# kitchen_timer.net
KiCad netlist of a schematic drawn in EAGLE
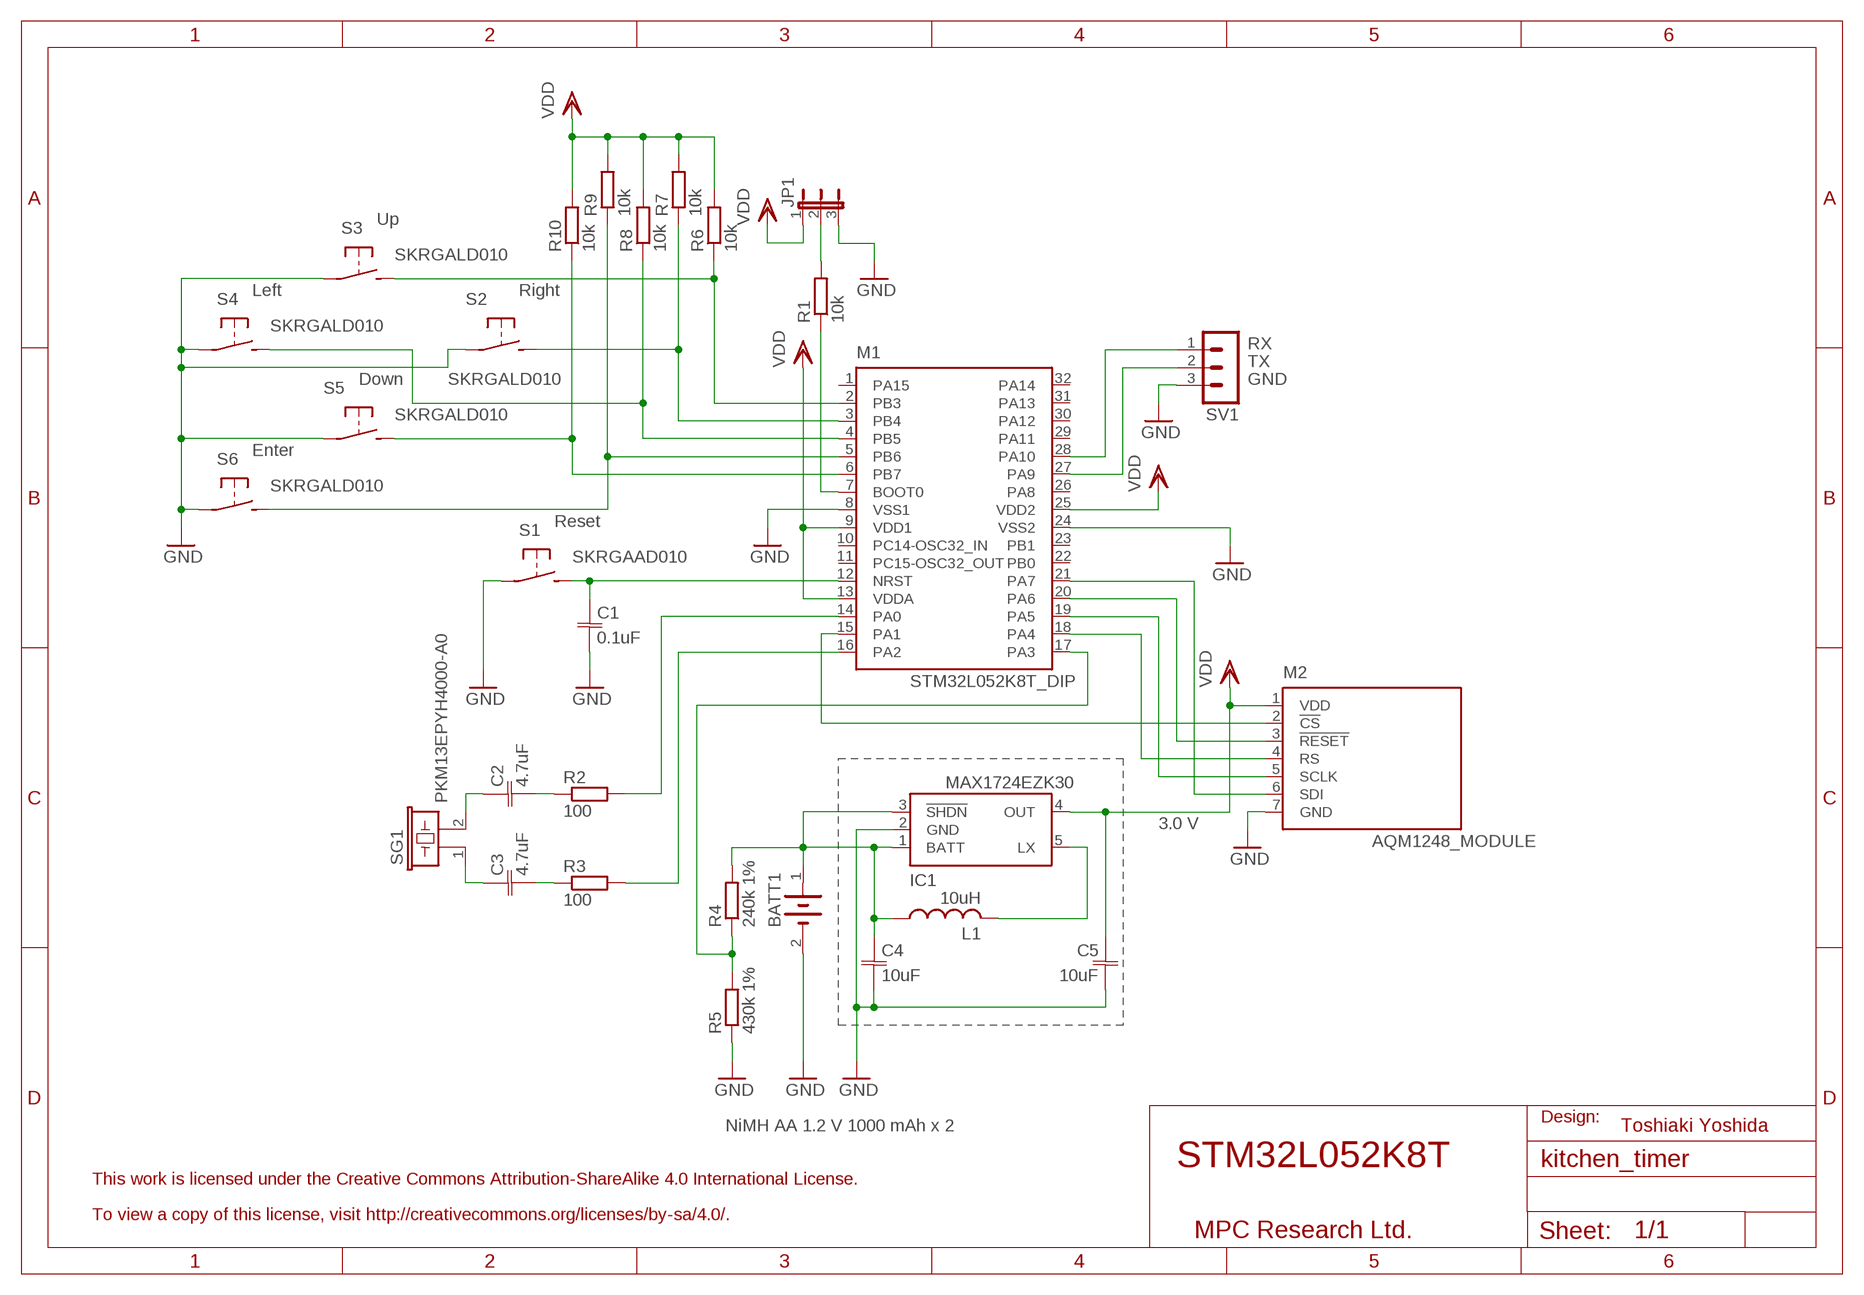
[diagram p0: schematic, sheet 1]

(export (version "E")
  (design (tool "Eeschema 10.0.6"))
  (components
    (comp (ref "BATT1")
      (value "NiMH AA 1.2 V 1000 mAh x 2")
      (footprint "eagle-import:TERMINAL")
      (libsource (lib "eagle-import") (part "BATTERY2"))
    )
    (comp (ref "C1")
      (value "0.1uF")
      (footprint "eagle-import:C050-024X044")
      (libsource (lib "eagle-import") (part "C-JIS050-024X044"))
    )
    (comp (ref "C2")
      (value "4.7uF")
      (footprint "eagle-import:C050-024X044")
      (libsource (lib "eagle-import") (part "C-JIS050-024X044"))
    )
    (comp (ref "C3")
      (value "4.7uF")
      (footprint "eagle-import:C050-024X044")
      (libsource (lib "eagle-import") (part "C-JIS050-024X044"))
    )
    (comp (ref "C4")
      (value "10uF")
      (footprint "eagle-import:C0603")
      (libsource (lib "eagle-import") (part "C-JIS0603"))
    )
    (comp (ref "C5")
      (value "10uF")
      (footprint "eagle-import:C0603")
      (libsource (lib "eagle-import") (part "C-JIS0603"))
    )
    (comp (ref "IC1")
      (value "MAX1724EZK30")
      (footprint "eagle-import:SOT23-5L")
      (libsource (lib "eagle-import") (part "MAX1724EZK30"))
    )
    (comp (ref "JP1")
      (value "JP2E")
      (footprint "eagle-import:JP2")
      (libsource (lib "eagle-import") (part "JP2E"))
    )
    (comp (ref "L1")
      (value "10uH")
      (footprint "eagle-import:L1812")
      (libsource (lib "eagle-import") (part "L-USL1812"))
    )
    (comp (ref "M1")
      (value "STM32L052K8T_DIP")
      (footprint "eagle-import:DIP32")
      (libsource (lib "eagle-import") (part "STM32L052K8T_DIP"))
    )
    (comp (ref "M2")
      (value "AQM1248_MODULE")
      (footprint "eagle-import:AQM1248")
      (libsource (lib "eagle-import") (part "AQM1248_MODULE"))
    )
    (comp (ref "R1")
      (value "10k")
      (footprint "eagle-import:0207_2V")
      (libsource (lib "eagle-import") (part "R-EU_0207/2V"))
    )
    (comp (ref "R2")
      (value "100")
      (footprint "eagle-import:0207_10")
      (libsource (lib "eagle-import") (part "R-EU_0207/10"))
    )
    (comp (ref "R3")
      (value "100")
      (footprint "eagle-import:0207_10")
      (libsource (lib "eagle-import") (part "R-EU_0207/10"))
    )
    (comp (ref "R4")
      (value "240k 1%")
      (footprint "eagle-import:0207_2V")
      (libsource (lib "eagle-import") (part "R-EU_0207/2V"))
    )
    (comp (ref "R5")
      (value "430k 1%")
      (footprint "eagle-import:0207_2V")
      (libsource (lib "eagle-import") (part "R-EU_0207/2V"))
    )
    (comp (ref "R6")
      (value "10k")
      (footprint "eagle-import:0207_7")
      (libsource (lib "eagle-import") (part "resistor_348_R-EU_0207/7"))
    )
    (comp (ref "R7")
      (value "10k")
      (footprint "eagle-import:0207_7")
      (libsource (lib "eagle-import") (part "resistor_348_R-EU_0207/7"))
    )
    (comp (ref "R8")
      (value "10k")
      (footprint "eagle-import:0207_7")
      (libsource (lib "eagle-import") (part "resistor_348_R-EU_0207/7"))
    )
    (comp (ref "R9")
      (value "10k")
      (footprint "eagle-import:0207_7")
      (libsource (lib "eagle-import") (part "resistor_348_R-EU_0207/7"))
    )
    (comp (ref "R10")
      (value "10k")
      (footprint "eagle-import:0207_7")
      (libsource (lib "eagle-import") (part "resistor_348_R-EU_0207/7"))
    )
    (comp (ref "S1")
      (value "SKRGAAD010")
      (footprint "eagle-import:SKRG")
      (libsource (lib "eagle-import") (part "SKRGAAD010"))
    )
    (comp (ref "S2")
      (value "SKRGALD010")
      (footprint "eagle-import:SKRG")
      (libsource (lib "eagle-import") (part "SKRGALD010"))
    )
    (comp (ref "S3")
      (value "SKRGALD010")
      (footprint "eagle-import:SKRG")
      (libsource (lib "eagle-import") (part "SKRGALD010"))
    )
    (comp (ref "S4")
      (value "SKRGALD010")
      (footprint "eagle-import:SKRG")
      (libsource (lib "eagle-import") (part "SKRGALD010"))
    )
    (comp (ref "S5")
      (value "SKRGALD010")
      (footprint "eagle-import:SKRG")
      (libsource (lib "eagle-import") (part "SKRGALD010"))
    )
    (comp (ref "S6")
      (value "SKRGALD010")
      (footprint "eagle-import:SKRG")
      (libsource (lib "eagle-import") (part "SKRGALD010"))
    )
    (comp (ref "SG1")
      (value "PKM13EPYH4000-A0")
      (footprint "eagle-import:EFBAA40D101")
      (libsource (lib "eagle-import") (part "EFB?AA40D101"))
    )
    (comp (ref "SV1")
      (value "MA03-1")
      (footprint "eagle-import:MA03-1")
      (libsource (lib "eagle-import") (part "MA03-1"))
    )
  )
  (nets
    (net (code "1") (name "GND") (class "Default")
      (node (ref "BATT1") (pin "2") (pinfunction "-_2") (pintype "passive"))
      (node (ref "C1") (pin "2") (pinfunction "2_2") (pintype "passive"))
      (node (ref "C4") (pin "2") (pinfunction "2_2") (pintype "passive"))
      (node (ref "C5") (pin "2") (pinfunction "2_2") (pintype "passive"))
      (node (ref "IC1") (pin "2") (pinfunction "GND_2") (pintype "power_in"))
      (node (ref "JP1") (pin "3") (pinfunction "3_3") (pintype "passive"))
      (node (ref "M1") (pin "24") (pinfunction "VSS2_24") (pintype "power_in"))
      (node (ref "M1") (pin "8") (pinfunction "VSS1_8") (pintype "power_in"))
      (node (ref "M2") (pin "7") (pinfunction "GND_7") (pintype "power_in"))
      (node (ref "R5") (pin "1") (pinfunction "1_1") (pintype "passive"))
      (node (ref "S1") (pin "P$1") (pinfunction "1_P$1") (pintype "passive"))
      (node (ref "S2") (pin "P$1") (pinfunction "1_P$1") (pintype "passive"))
      (node (ref "S3") (pin "P$1") (pinfunction "1_P$1") (pintype "passive"))
      (node (ref "S4") (pin "P$1") (pinfunction "1_P$1") (pintype "passive"))
      (node (ref "S5") (pin "P$1") (pinfunction "1_P$1") (pintype "passive"))
      (node (ref "S6") (pin "P$1") (pinfunction "1_P$1") (pintype "passive"))
      (node (ref "SV1") (pin "3") (pinfunction "3_3") (pintype "passive"))
    )
    (net (code "2") (name "Net-(BATT1-+)") (class "Default")
      (node (ref "BATT1") (pin "1") (pinfunction "+_1") (pintype "passive"))
      (node (ref "C4") (pin "1") (pinfunction "1_1") (pintype "passive"))
      (node (ref "IC1") (pin "1") (pinfunction "BATT_1") (pintype "power_in"))
      (node (ref "IC1") (pin "3") (pinfunction "~{SHDN}_3") (pintype "input"))
      (node (ref "L1") (pin "1") (pinfunction "1_1") (pintype "passive"))
      (node (ref "R4") (pin "2") (pinfunction "2_2") (pintype "passive"))
    )
    (net (code "3") (name "Net-(C2-Pad1)") (class "Default")
      (node (ref "C2") (pin "1") (pinfunction "1_1") (pintype "passive"))
      (node (ref "SG1") (pin "2") (pinfunction "2_2") (pintype "passive"))
    )
    (net (code "4") (name "Net-(C2-Pad2)") (class "Default")
      (node (ref "C2") (pin "2") (pinfunction "2_2") (pintype "passive"))
      (node (ref "R2") (pin "1") (pinfunction "1_1") (pintype "passive"))
    )
    (net (code "5") (name "Net-(C3-Pad1)") (class "Default")
      (node (ref "C3") (pin "1") (pinfunction "1_1") (pintype "passive"))
      (node (ref "SG1") (pin "1") (pinfunction "1_1") (pintype "passive"))
    )
    (net (code "6") (name "Net-(C3-Pad2)") (class "Default")
      (node (ref "C3") (pin "2") (pinfunction "2_2") (pintype "passive"))
      (node (ref "R3") (pin "1") (pinfunction "1_1") (pintype "passive"))
    )
    (net (code "7") (name "Net-(IC1-LX)") (class "Default")
      (node (ref "IC1") (pin "5") (pinfunction "LX_5") (pintype "bidirectional"))
      (node (ref "L1") (pin "2") (pinfunction "2_2") (pintype "passive"))
    )
    (net (code "8") (name "Net-(JP1-Pad2)") (class "Default")
      (node (ref "JP1") (pin "2") (pinfunction "2_2") (pintype "passive"))
      (node (ref "R1") (pin "2") (pinfunction "2_2") (pintype "passive"))
    )
    (net (code "9") (name "Net-(M1-BOOT0)") (class "Default")
      (node (ref "M1") (pin "7") (pinfunction "BOOT0_7") (pintype "bidirectional"))
      (node (ref "R1") (pin "1") (pinfunction "1_1") (pintype "passive"))
    )
    (net (code "10") (name "Net-(M1-NRST)") (class "Default")
      (node (ref "C1") (pin "1") (pinfunction "1_1") (pintype "passive"))
      (node (ref "M1") (pin "12") (pinfunction "NRST_12") (pintype "bidirectional"))
      (node (ref "S1") (pin "P$2") (pinfunction "2_P$2") (pintype "passive"))
    )
    (net (code "11") (name "Net-(M1-PA0)") (class "Default")
      (node (ref "M1") (pin "14") (pinfunction "PA0_14") (pintype "bidirectional"))
      (node (ref "R2") (pin "2") (pinfunction "2_2") (pintype "passive"))
    )
    (net (code "12") (name "Net-(M1-PA1)") (class "Default")
      (node (ref "M1") (pin "15") (pinfunction "PA1_15") (pintype "bidirectional"))
      (node (ref "M2") (pin "2") (pinfunction "~{CS}_2") (pintype "input"))
    )
    (net (code "13") (name "Net-(M1-PA2)") (class "Default")
      (node (ref "M1") (pin "16") (pinfunction "PA2_16") (pintype "bidirectional"))
      (node (ref "R3") (pin "2") (pinfunction "2_2") (pintype "passive"))
    )
    (net (code "14") (name "Net-(M1-PA3)") (class "Default")
      (node (ref "M1") (pin "17") (pinfunction "PA3_17") (pintype "bidirectional"))
      (node (ref "R4") (pin "1") (pinfunction "1_1") (pintype "passive"))
      (node (ref "R5") (pin "2") (pinfunction "2_2") (pintype "passive"))
    )
    (net (code "15") (name "Net-(M1-PA4)") (class "Default")
      (node (ref "M1") (pin "18") (pinfunction "PA4_18") (pintype "bidirectional"))
      (node (ref "M2") (pin "4") (pinfunction "RS_4") (pintype "input"))
    )
    (net (code "16") (name "Net-(M1-PA5)") (class "Default")
      (node (ref "M1") (pin "19") (pinfunction "PA5_19") (pintype "bidirectional"))
      (node (ref "M2") (pin "5") (pinfunction "SCLK_5") (pintype "input"))
    )
    (net (code "17") (name "Net-(M1-PA6)") (class "Default")
      (node (ref "M1") (pin "20") (pinfunction "PA6_20") (pintype "bidirectional"))
      (node (ref "M2") (pin "3") (pinfunction "~{RESET}_3") (pintype "input"))
    )
    (net (code "18") (name "Net-(M1-PA7)") (class "Default")
      (node (ref "M1") (pin "21") (pinfunction "PA7_21") (pintype "bidirectional"))
      (node (ref "M2") (pin "6") (pinfunction "SDI_6") (pintype "input"))
    )
    (net (code "19") (name "Net-(M1-PA9)") (class "Default")
      (node (ref "M1") (pin "27") (pinfunction "PA9_27") (pintype "bidirectional"))
      (node (ref "SV1") (pin "2") (pinfunction "2_2") (pintype "passive"))
    )
    (net (code "20") (name "Net-(M1-PA10)") (class "Default")
      (node (ref "M1") (pin "28") (pinfunction "PA10_28") (pintype "bidirectional"))
      (node (ref "SV1") (pin "1") (pinfunction "1_1") (pintype "passive"))
    )
    (net (code "21") (name "Net-(M1-PB3)") (class "Default")
      (node (ref "M1") (pin "2") (pinfunction "PB3_2") (pintype "bidirectional"))
      (node (ref "R6") (pin "1") (pinfunction "1_1") (pintype "passive"))
      (node (ref "S3") (pin "P$2") (pinfunction "2_P$2") (pintype "passive"))
    )
    (net (code "22") (name "Net-(M1-PB4)") (class "Default")
      (node (ref "M1") (pin "3") (pinfunction "PB4_3") (pintype "bidirectional"))
      (node (ref "R7") (pin "1") (pinfunction "1_1") (pintype "passive"))
      (node (ref "S2") (pin "P$2") (pinfunction "2_P$2") (pintype "passive"))
    )
    (net (code "23") (name "Net-(M1-PB5)") (class "Default")
      (node (ref "M1") (pin "4") (pinfunction "PB5_4") (pintype "bidirectional"))
      (node (ref "R8") (pin "1") (pinfunction "1_1") (pintype "passive"))
      (node (ref "S4") (pin "P$2") (pinfunction "2_P$2") (pintype "passive"))
    )
    (net (code "24") (name "Net-(M1-PB6)") (class "Default")
      (node (ref "M1") (pin "5") (pinfunction "PB6_5") (pintype "bidirectional"))
      (node (ref "R9") (pin "1") (pinfunction "1_1") (pintype "passive"))
      (node (ref "S6") (pin "P$2") (pinfunction "2_P$2") (pintype "passive"))
    )
    (net (code "25") (name "Net-(M1-PB7)") (class "Default")
      (node (ref "M1") (pin "6") (pinfunction "PB7_6") (pintype "bidirectional"))
      (node (ref "R10") (pin "1") (pinfunction "1_1") (pintype "passive"))
      (node (ref "S5") (pin "P$2") (pinfunction "2_P$2") (pintype "passive"))
    )
    (net (code "26") (name "VDD") (class "Default")
      (node (ref "C5") (pin "1") (pinfunction "1_1") (pintype "passive"))
      (node (ref "IC1") (pin "4") (pinfunction "OUT_4") (pintype "power_in"))
      (node (ref "JP1") (pin "1") (pinfunction "1_1") (pintype "passive"))
      (node (ref "M1") (pin "13") (pinfunction "VDDA_13") (pintype "power_in"))
      (node (ref "M1") (pin "25") (pinfunction "VDD2_25") (pintype "bidirectional"))
      (node (ref "M1") (pin "9") (pinfunction "VDD1_9") (pintype "power_in"))
      (node (ref "M2") (pin "1") (pinfunction "VDD_1") (pintype "power_in"))
      (node (ref "R10") (pin "2") (pinfunction "2_2") (pintype "passive"))
      (node (ref "R6") (pin "2") (pinfunction "2_2") (pintype "passive"))
      (node (ref "R7") (pin "2") (pinfunction "2_2") (pintype "passive"))
      (node (ref "R8") (pin "2") (pinfunction "2_2") (pintype "passive"))
      (node (ref "R9") (pin "2") (pinfunction "2_2") (pintype "passive"))
    )
    (net (code "27") (name "unconnected-(M1-PA8-Pad26)") (class "Default")
      (node (ref "M1") (pin "26") (pinfunction "PA8_26") (pintype "bidirectional"))
    )
    (net (code "28") (name "unconnected-(M1-PA11-Pad29)") (class "Default")
      (node (ref "M1") (pin "29") (pinfunction "PA11_29") (pintype "bidirectional"))
    )
    (net (code "29") (name "unconnected-(M1-PA12-Pad30)") (class "Default")
      (node (ref "M1") (pin "30") (pinfunction "PA12_30") (pintype "bidirectional"))
    )
    (net (code "30") (name "unconnected-(M1-PA13-Pad31)") (class "Default")
      (node (ref "M1") (pin "31") (pinfunction "PA13_31") (pintype "bidirectional"))
    )
    (net (code "31") (name "unconnected-(M1-PA14-Pad32)") (class "Default")
      (node (ref "M1") (pin "32") (pinfunction "PA14_32") (pintype "bidirectional"))
    )
    (net (code "32") (name "unconnected-(M1-PA15-Pad1)") (class "Default")
      (node (ref "M1") (pin "1") (pinfunction "PA15_1") (pintype "bidirectional"))
    )
    (net (code "33") (name "unconnected-(M1-PB0-Pad22)") (class "Default")
      (node (ref "M1") (pin "22") (pinfunction "PB0_22") (pintype "bidirectional"))
    )
    (net (code "34") (name "unconnected-(M1-PB1-Pad23)") (class "Default")
      (node (ref "M1") (pin "23") (pinfunction "PB1_23") (pintype "bidirectional"))
    )
    (net (code "35") (name "unconnected-(M1-PC14-OSC32_IN-Pad10)") (class "Default")
      (node (ref "M1") (pin "10") (pinfunction "PC14-OSC32_IN_10") (pintype "bidirectional"))
    )
    (net (code "36") (name "unconnected-(M1-PC15-OSC32_OUT-Pad11)") (class "Default")
      (node (ref "M1") (pin "11") (pinfunction "PC15-OSC32_OUT_11") (pintype "bidirectional"))
    )
  )
)
